# SCH_ESPHome-Aldes-T_One-Basic-v1_0_2024-.net
KiCad netlist of a schematic drawn in EasyEDA
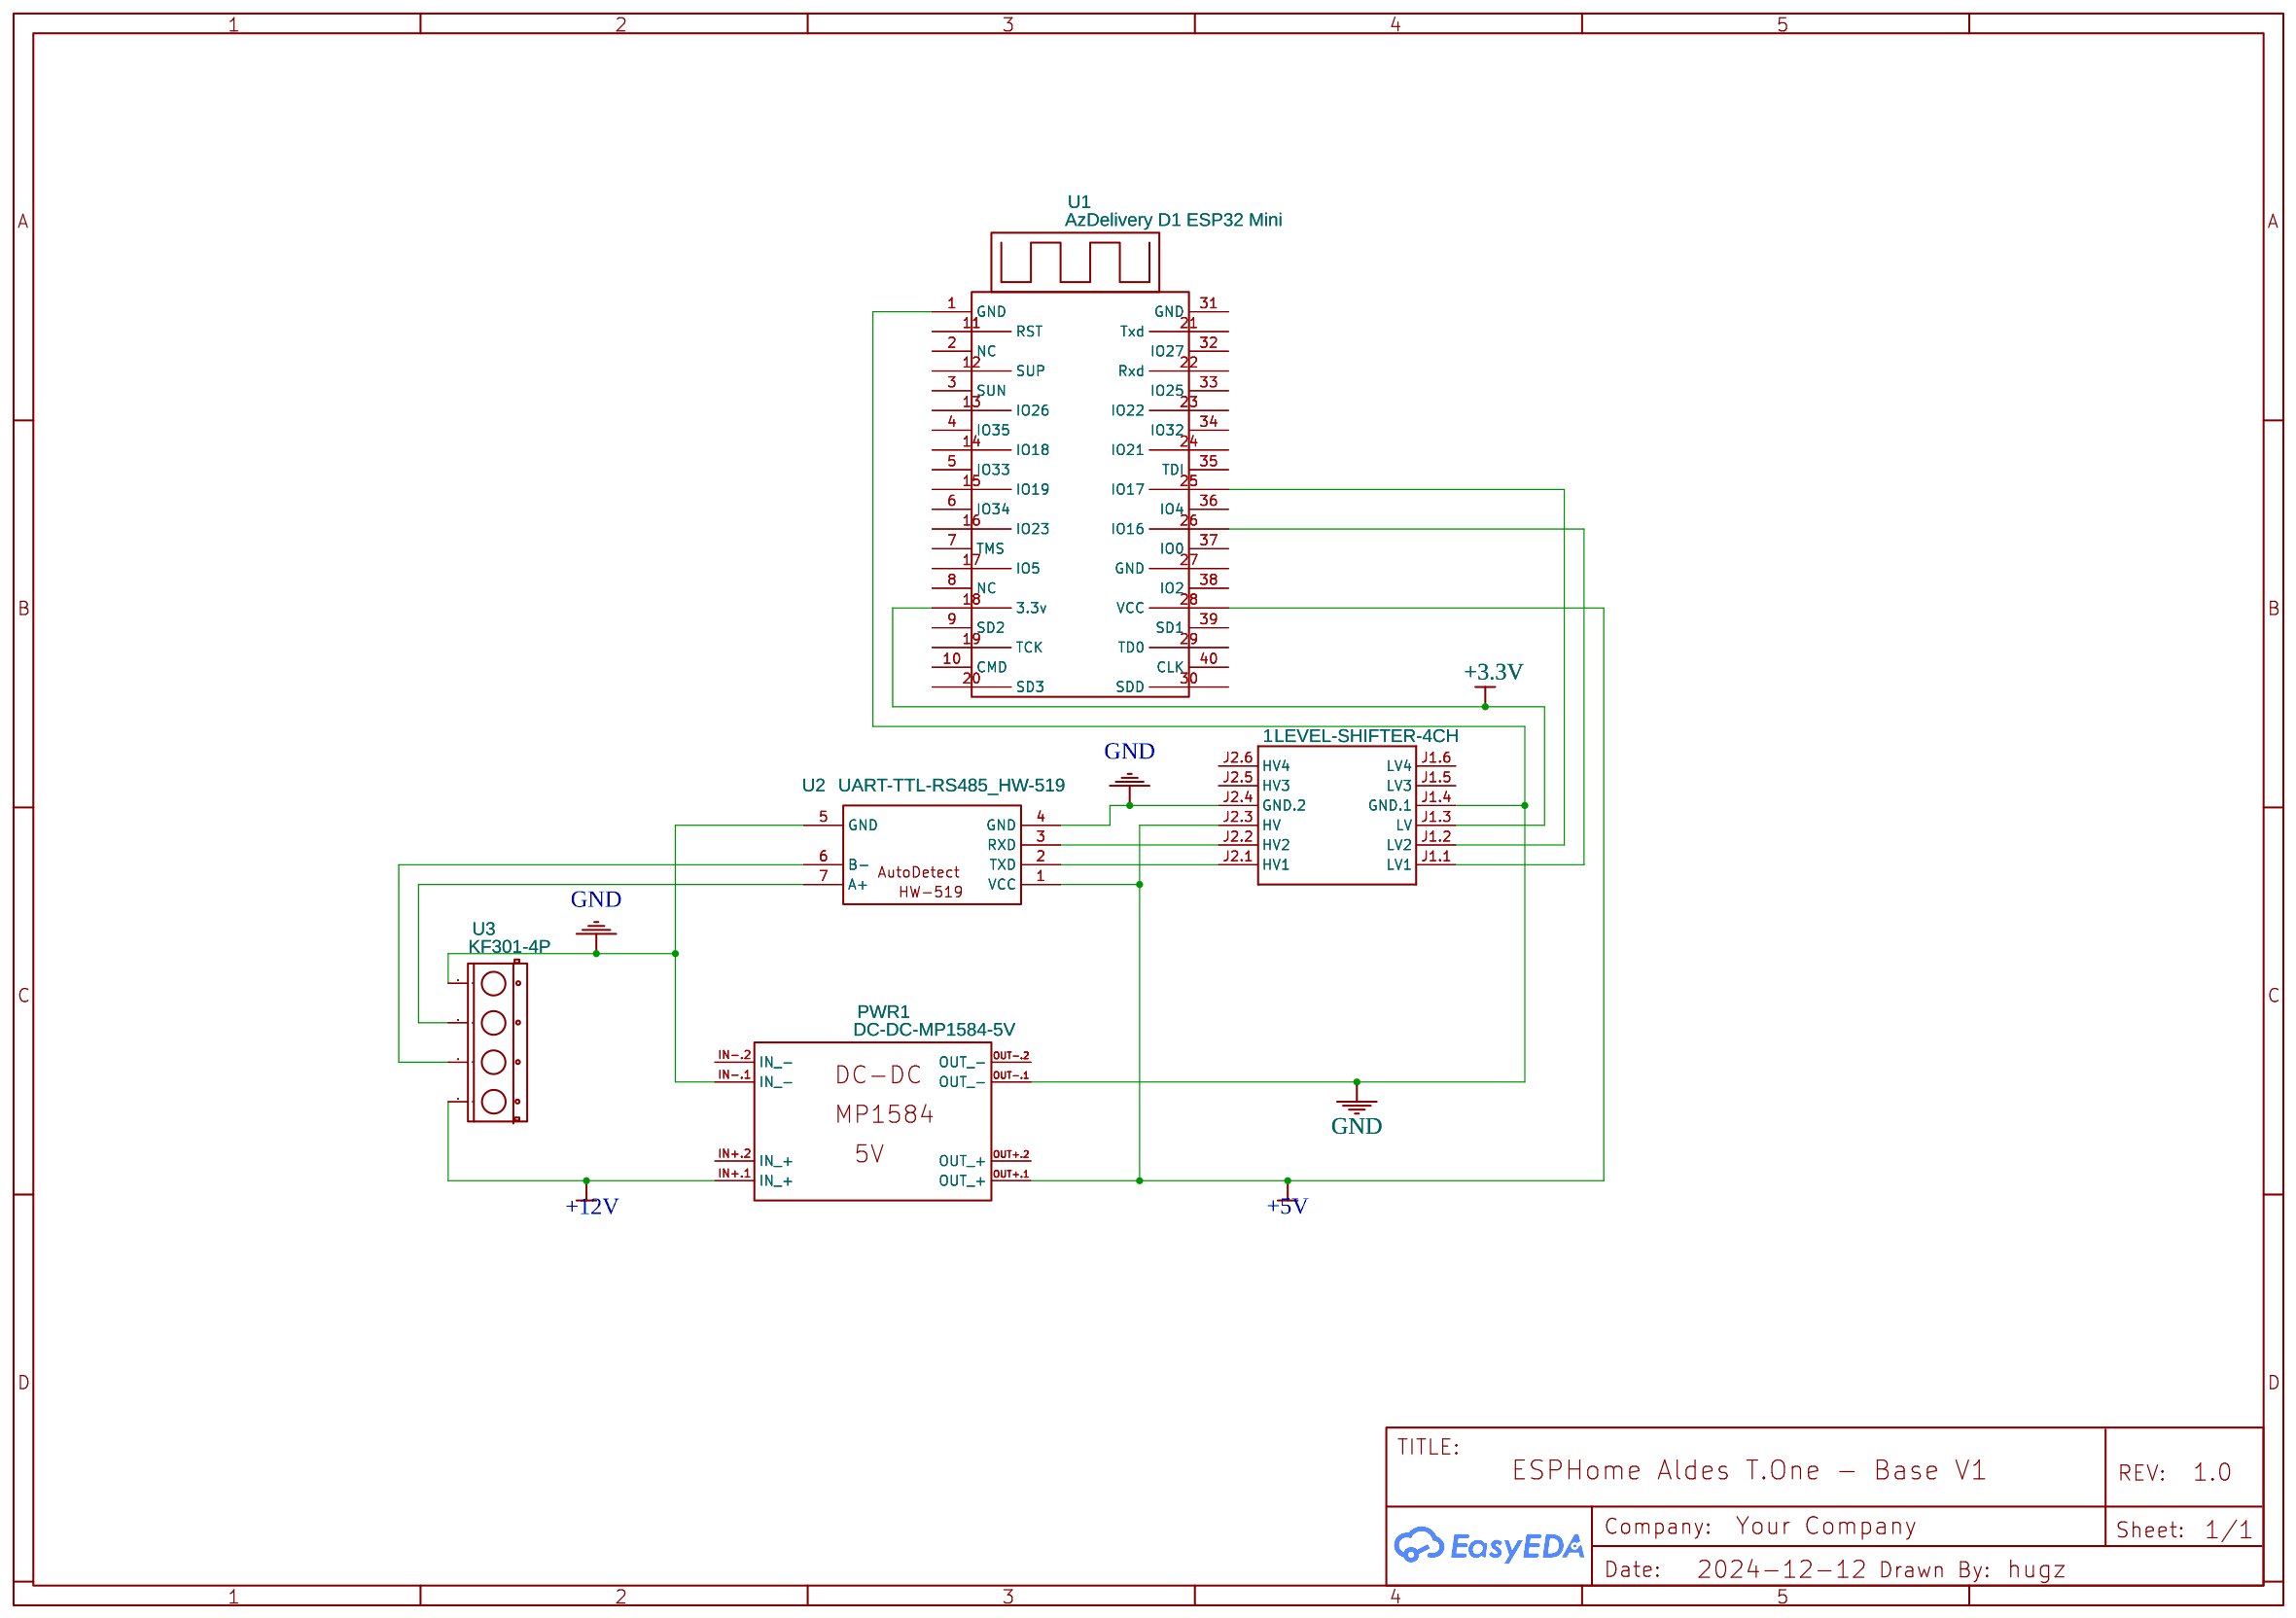
[diagram p0: schematic sheet]

(export (version "E")
  (design (tool "Eeschema 10.0.6"))
  (components
    (comp (ref "1") (value "LEVEL-SHIFTER-4CH") (libsource (lib "") (part "LEVEL-SHIFTER-4CH")))
    (comp (ref "PWR1") (value "DC-DC-MP1584-5V") (libsource (lib "") (part "DC-DC-MP1584-5V")))
    (comp (ref "U1")
      (value "AzDelivery D1 ESP32 Mini")
      (fields (field (name "Manufacturer Part") "D1 Mini ESP32") (field (name "Manufacturer") "AzDelivery"))
      (libsource (lib "") (part "AzDelivery D1 ESP32 Mini"))
    )
    (comp (ref "U2") (value "UART-TTL-RS485_HW-519") (libsource (lib "") (part "UART-TTL-RS485_HW-519")))
    (comp (ref "U3")
      (value "KF301-4P")
      (fields (field (name "Manufacturer Part") "KF301"))
      (libsource (lib "") (part "KF301-4P"))
    )
  )
  (nets
    (net (code "1") (name "+3.3V") (class "Default")
      (node (ref "1") (pin "J1.3") (pinfunction "LV_J1.3") (pintype "bidirectional"))
      (node (ref "U1") (pin "18") (pinfunction "3.3v_18") (pintype "unspecified"))
    )
    (net (code "2") (name "+5V") (class "Default")
      (node (ref "1") (pin "J2.3") (pinfunction "HV_J2.3") (pintype "bidirectional"))
      (node (ref "PWR1") (pin "OUT+.1") (pinfunction "OUT_+_OUT+.1") (pintype "unspecified"))
      (node (ref "U1") (pin "28") (pinfunction "VCC_28") (pintype "unspecified"))
      (node (ref "U2") (pin "1") (pinfunction "VCC_1") (pintype "unspecified"))
    )
    (net (code "3") (name "+12V") (class "Default")
      (node (ref "PWR1") (pin "IN+.1") (pinfunction "IN_+_IN+.1") (pintype "unspecified"))
      (node (ref "U3") (pin "4") (pinfunction "4_4") (pintype "unspecified"))
    )
    (net (code "4") (name "GND") (class "Default")
      (node (ref "1") (pin "J1.4") (pinfunction "GND.1_J1.4") (pintype "bidirectional"))
      (node (ref "1") (pin "J2.4") (pinfunction "GND.2_J2.4") (pintype "bidirectional"))
      (node (ref "PWR1") (pin "IN-.1") (pinfunction "IN_-_IN-.1") (pintype "unspecified"))
      (node (ref "PWR1") (pin "OUT-.1") (pinfunction "OUT_-_OUT-.1") (pintype "unspecified"))
      (node (ref "U1") (pin "1") (pinfunction "GND_1") (pintype "unspecified"))
      (node (ref "U2") (pin "4") (pinfunction "GND_4") (pintype "unspecified"))
      (node (ref "U2") (pin "5") (pinfunction "GND_5") (pintype "unspecified"))
      (node (ref "U3") (pin "1") (pinfunction "1_1") (pintype "unspecified"))
    )
    (net (code "5") (name "Net-(1-HV1)") (class "Default")
      (node (ref "1") (pin "J2.1") (pinfunction "HV1_J2.1") (pintype "bidirectional"))
      (node (ref "U2") (pin "2") (pinfunction "TXD_2") (pintype "unspecified"))
    )
    (net (code "6") (name "Net-(1-HV2)") (class "Default")
      (node (ref "1") (pin "J2.2") (pinfunction "HV2_J2.2") (pintype "bidirectional"))
      (node (ref "U2") (pin "3") (pinfunction "RXD_3") (pintype "unspecified"))
    )
    (net (code "7") (name "Net-(1-LV1)") (class "Default")
      (node (ref "1") (pin "J1.1") (pinfunction "LV1_J1.1") (pintype "bidirectional"))
      (node (ref "U1") (pin "26") (pinfunction "IO16_26") (pintype "unspecified"))
    )
    (net (code "8") (name "Net-(1-LV2)") (class "Default")
      (node (ref "1") (pin "J1.2") (pinfunction "LV2_J1.2") (pintype "bidirectional"))
      (node (ref "U1") (pin "25") (pinfunction "IO17_25") (pintype "unspecified"))
    )
    (net (code "9") (name "Net-(U2-A+)") (class "Default")
      (node (ref "U2") (pin "7") (pinfunction "A+_7") (pintype "unspecified"))
      (node (ref "U3") (pin "2") (pinfunction "2_2") (pintype "unspecified"))
    )
    (net (code "10") (name "Net-(U2-B-)") (class "Default")
      (node (ref "U2") (pin "6") (pinfunction "B-_6") (pintype "unspecified"))
      (node (ref "U3") (pin "3") (pinfunction "3_3") (pintype "unspecified"))
    )
    (net (code "11") (name "unconnected-(1-HV3-PadJ2.5)") (class "Default")
      (node (ref "1") (pin "J2.5") (pinfunction "HV3_J2.5") (pintype "bidirectional"))
    )
    (net (code "12") (name "unconnected-(1-HV4-PadJ2.6)") (class "Default")
      (node (ref "1") (pin "J2.6") (pinfunction "HV4_J2.6") (pintype "bidirectional"))
    )
    (net (code "13") (name "unconnected-(1-LV3-PadJ1.5)") (class "Default")
      (node (ref "1") (pin "J1.5") (pinfunction "LV3_J1.5") (pintype "bidirectional"))
    )
    (net (code "14") (name "unconnected-(1-LV4-PadJ1.6)") (class "Default")
      (node (ref "1") (pin "J1.6") (pinfunction "LV4_J1.6") (pintype "bidirectional"))
    )
    (net (code "15") (name "unconnected-(PWR1-IN_+-PadIN+.2)") (class "Default")
      (node (ref "PWR1") (pin "IN+.2") (pinfunction "IN_+_IN+.2") (pintype "unspecified"))
    )
    (net (code "16") (name "unconnected-(PWR1-IN_--PadIN-.2)") (class "Default")
      (node (ref "PWR1") (pin "IN-.2") (pinfunction "IN_-_IN-.2") (pintype "unspecified"))
    )
    (net (code "17") (name "unconnected-(PWR1-OUT_+-PadOUT+.2)") (class "Default")
      (node (ref "PWR1") (pin "OUT+.2") (pinfunction "OUT_+_OUT+.2") (pintype "unspecified"))
    )
    (net (code "18") (name "unconnected-(PWR1-OUT_--PadOUT-.2)") (class "Default")
      (node (ref "PWR1") (pin "OUT-.2") (pinfunction "OUT_-_OUT-.2") (pintype "unspecified"))
    )
    (net (code "19") (name "unconnected-(U1-CLK-Pad40)") (class "Default")
      (node (ref "U1") (pin "40") (pinfunction "CLK_40") (pintype "unspecified"))
    )
    (net (code "20") (name "unconnected-(U1-CMD-Pad10)") (class "Default")
      (node (ref "U1") (pin "10") (pinfunction "CMD_10") (pintype "unspecified"))
    )
    (net (code "21") (name "unconnected-(U1-GND-Pad27)") (class "Default")
      (node (ref "U1") (pin "27") (pinfunction "GND_27") (pintype "unspecified"))
    )
    (net (code "22") (name "unconnected-(U1-GND-Pad31)") (class "Default")
      (node (ref "U1") (pin "31") (pinfunction "GND_31") (pintype "unspecified"))
    )
    (net (code "23") (name "unconnected-(U1-IO0-Pad37)") (class "Default")
      (node (ref "U1") (pin "37") (pinfunction "IO0_37") (pintype "unspecified"))
    )
    (net (code "24") (name "unconnected-(U1-IO2-Pad38)") (class "Default")
      (node (ref "U1") (pin "38") (pinfunction "IO2_38") (pintype "unspecified"))
    )
    (net (code "25") (name "unconnected-(U1-IO4-Pad36)") (class "Default")
      (node (ref "U1") (pin "36") (pinfunction "IO4_36") (pintype "unspecified"))
    )
    (net (code "26") (name "unconnected-(U1-IO5-Pad17)") (class "Default")
      (node (ref "U1") (pin "17") (pinfunction "IO5_17") (pintype "unspecified"))
    )
    (net (code "27") (name "unconnected-(U1-IO18-Pad14)") (class "Default")
      (node (ref "U1") (pin "14") (pinfunction "IO18_14") (pintype "unspecified"))
    )
    (net (code "28") (name "unconnected-(U1-IO19-Pad15)") (class "Default")
      (node (ref "U1") (pin "15") (pinfunction "IO19_15") (pintype "unspecified"))
    )
    (net (code "29") (name "unconnected-(U1-IO21-Pad24)") (class "Default")
      (node (ref "U1") (pin "24") (pinfunction "IO21_24") (pintype "unspecified"))
    )
    (net (code "30") (name "unconnected-(U1-IO22-Pad23)") (class "Default")
      (node (ref "U1") (pin "23") (pinfunction "IO22_23") (pintype "unspecified"))
    )
    (net (code "31") (name "unconnected-(U1-IO23-Pad16)") (class "Default")
      (node (ref "U1") (pin "16") (pinfunction "IO23_16") (pintype "unspecified"))
    )
    (net (code "32") (name "unconnected-(U1-IO25-Pad33)") (class "Default")
      (node (ref "U1") (pin "33") (pinfunction "IO25_33") (pintype "unspecified"))
    )
    (net (code "33") (name "unconnected-(U1-IO26-Pad13)") (class "Default")
      (node (ref "U1") (pin "13") (pinfunction "IO26_13") (pintype "unspecified"))
    )
    (net (code "34") (name "unconnected-(U1-IO27-Pad32)") (class "Default")
      (node (ref "U1") (pin "32") (pinfunction "IO27_32") (pintype "unspecified"))
    )
    (net (code "35") (name "unconnected-(U1-IO32-Pad34)") (class "Default")
      (node (ref "U1") (pin "34") (pinfunction "IO32_34") (pintype "unspecified"))
    )
    (net (code "36") (name "unconnected-(U1-IO33-Pad5)") (class "Default")
      (node (ref "U1") (pin "5") (pinfunction "IO33_5") (pintype "unspecified"))
    )
    (net (code "37") (name "unconnected-(U1-IO34-Pad6)") (class "Default")
      (node (ref "U1") (pin "6") (pinfunction "IO34_6") (pintype "unspecified"))
    )
    (net (code "38") (name "unconnected-(U1-IO35-Pad4)") (class "Default")
      (node (ref "U1") (pin "4") (pinfunction "IO35_4") (pintype "unspecified"))
    )
    (net (code "39") (name "unconnected-(U1-NC-Pad2)") (class "Default")
      (node (ref "U1") (pin "2") (pinfunction "NC_2") (pintype "unspecified"))
    )
    (net (code "40") (name "unconnected-(U1-NC-Pad8)") (class "Default")
      (node (ref "U1") (pin "8") (pinfunction "NC_8") (pintype "unspecified"))
    )
    (net (code "41") (name "unconnected-(U1-RST-Pad11)") (class "Default")
      (node (ref "U1") (pin "11") (pinfunction "RST_11") (pintype "unspecified"))
    )
    (net (code "42") (name "unconnected-(U1-Rxd-Pad22)") (class "Default")
      (node (ref "U1") (pin "22") (pinfunction "Rxd_22") (pintype "unspecified"))
    )
    (net (code "43") (name "unconnected-(U1-SD1-Pad39)") (class "Default")
      (node (ref "U1") (pin "39") (pinfunction "SD1_39") (pintype "unspecified"))
    )
    (net (code "44") (name "unconnected-(U1-SD2-Pad9)") (class "Default")
      (node (ref "U1") (pin "9") (pinfunction "SD2_9") (pintype "unspecified"))
    )
    (net (code "45") (name "unconnected-(U1-SD3-Pad20)") (class "Default")
      (node (ref "U1") (pin "20") (pinfunction "SD3_20") (pintype "unspecified"))
    )
    (net (code "46") (name "unconnected-(U1-SDD-Pad30)") (class "Default")
      (node (ref "U1") (pin "30") (pinfunction "SDD_30") (pintype "unspecified"))
    )
    (net (code "47") (name "unconnected-(U1-SUN-Pad3)") (class "Default")
      (node (ref "U1") (pin "3") (pinfunction "SUN_3") (pintype "unspecified"))
    )
    (net (code "48") (name "unconnected-(U1-SUP-Pad12)") (class "Default")
      (node (ref "U1") (pin "12") (pinfunction "SUP_12") (pintype "unspecified"))
    )
    (net (code "49") (name "unconnected-(U1-TCK-Pad19)") (class "Default")
      (node (ref "U1") (pin "19") (pinfunction "TCK_19") (pintype "unspecified"))
    )
    (net (code "50") (name "unconnected-(U1-TD0-Pad29)") (class "Default")
      (node (ref "U1") (pin "29") (pinfunction "TD0_29") (pintype "unspecified"))
    )
    (net (code "51") (name "unconnected-(U1-TDI-Pad35)") (class "Default")
      (node (ref "U1") (pin "35") (pinfunction "TDI_35") (pintype "unspecified"))
    )
    (net (code "52") (name "unconnected-(U1-TMS-Pad7)") (class "Default")
      (node (ref "U1") (pin "7") (pinfunction "TMS_7") (pintype "unspecified"))
    )
    (net (code "53") (name "unconnected-(U1-Txd-Pad21)") (class "Default")
      (node (ref "U1") (pin "21") (pinfunction "Txd_21") (pintype "unspecified"))
    )
  )
)
